# ProPrj_STM32__2025-03-02.net
KiCad netlist of a schematic drawn in EasyEDA Pro
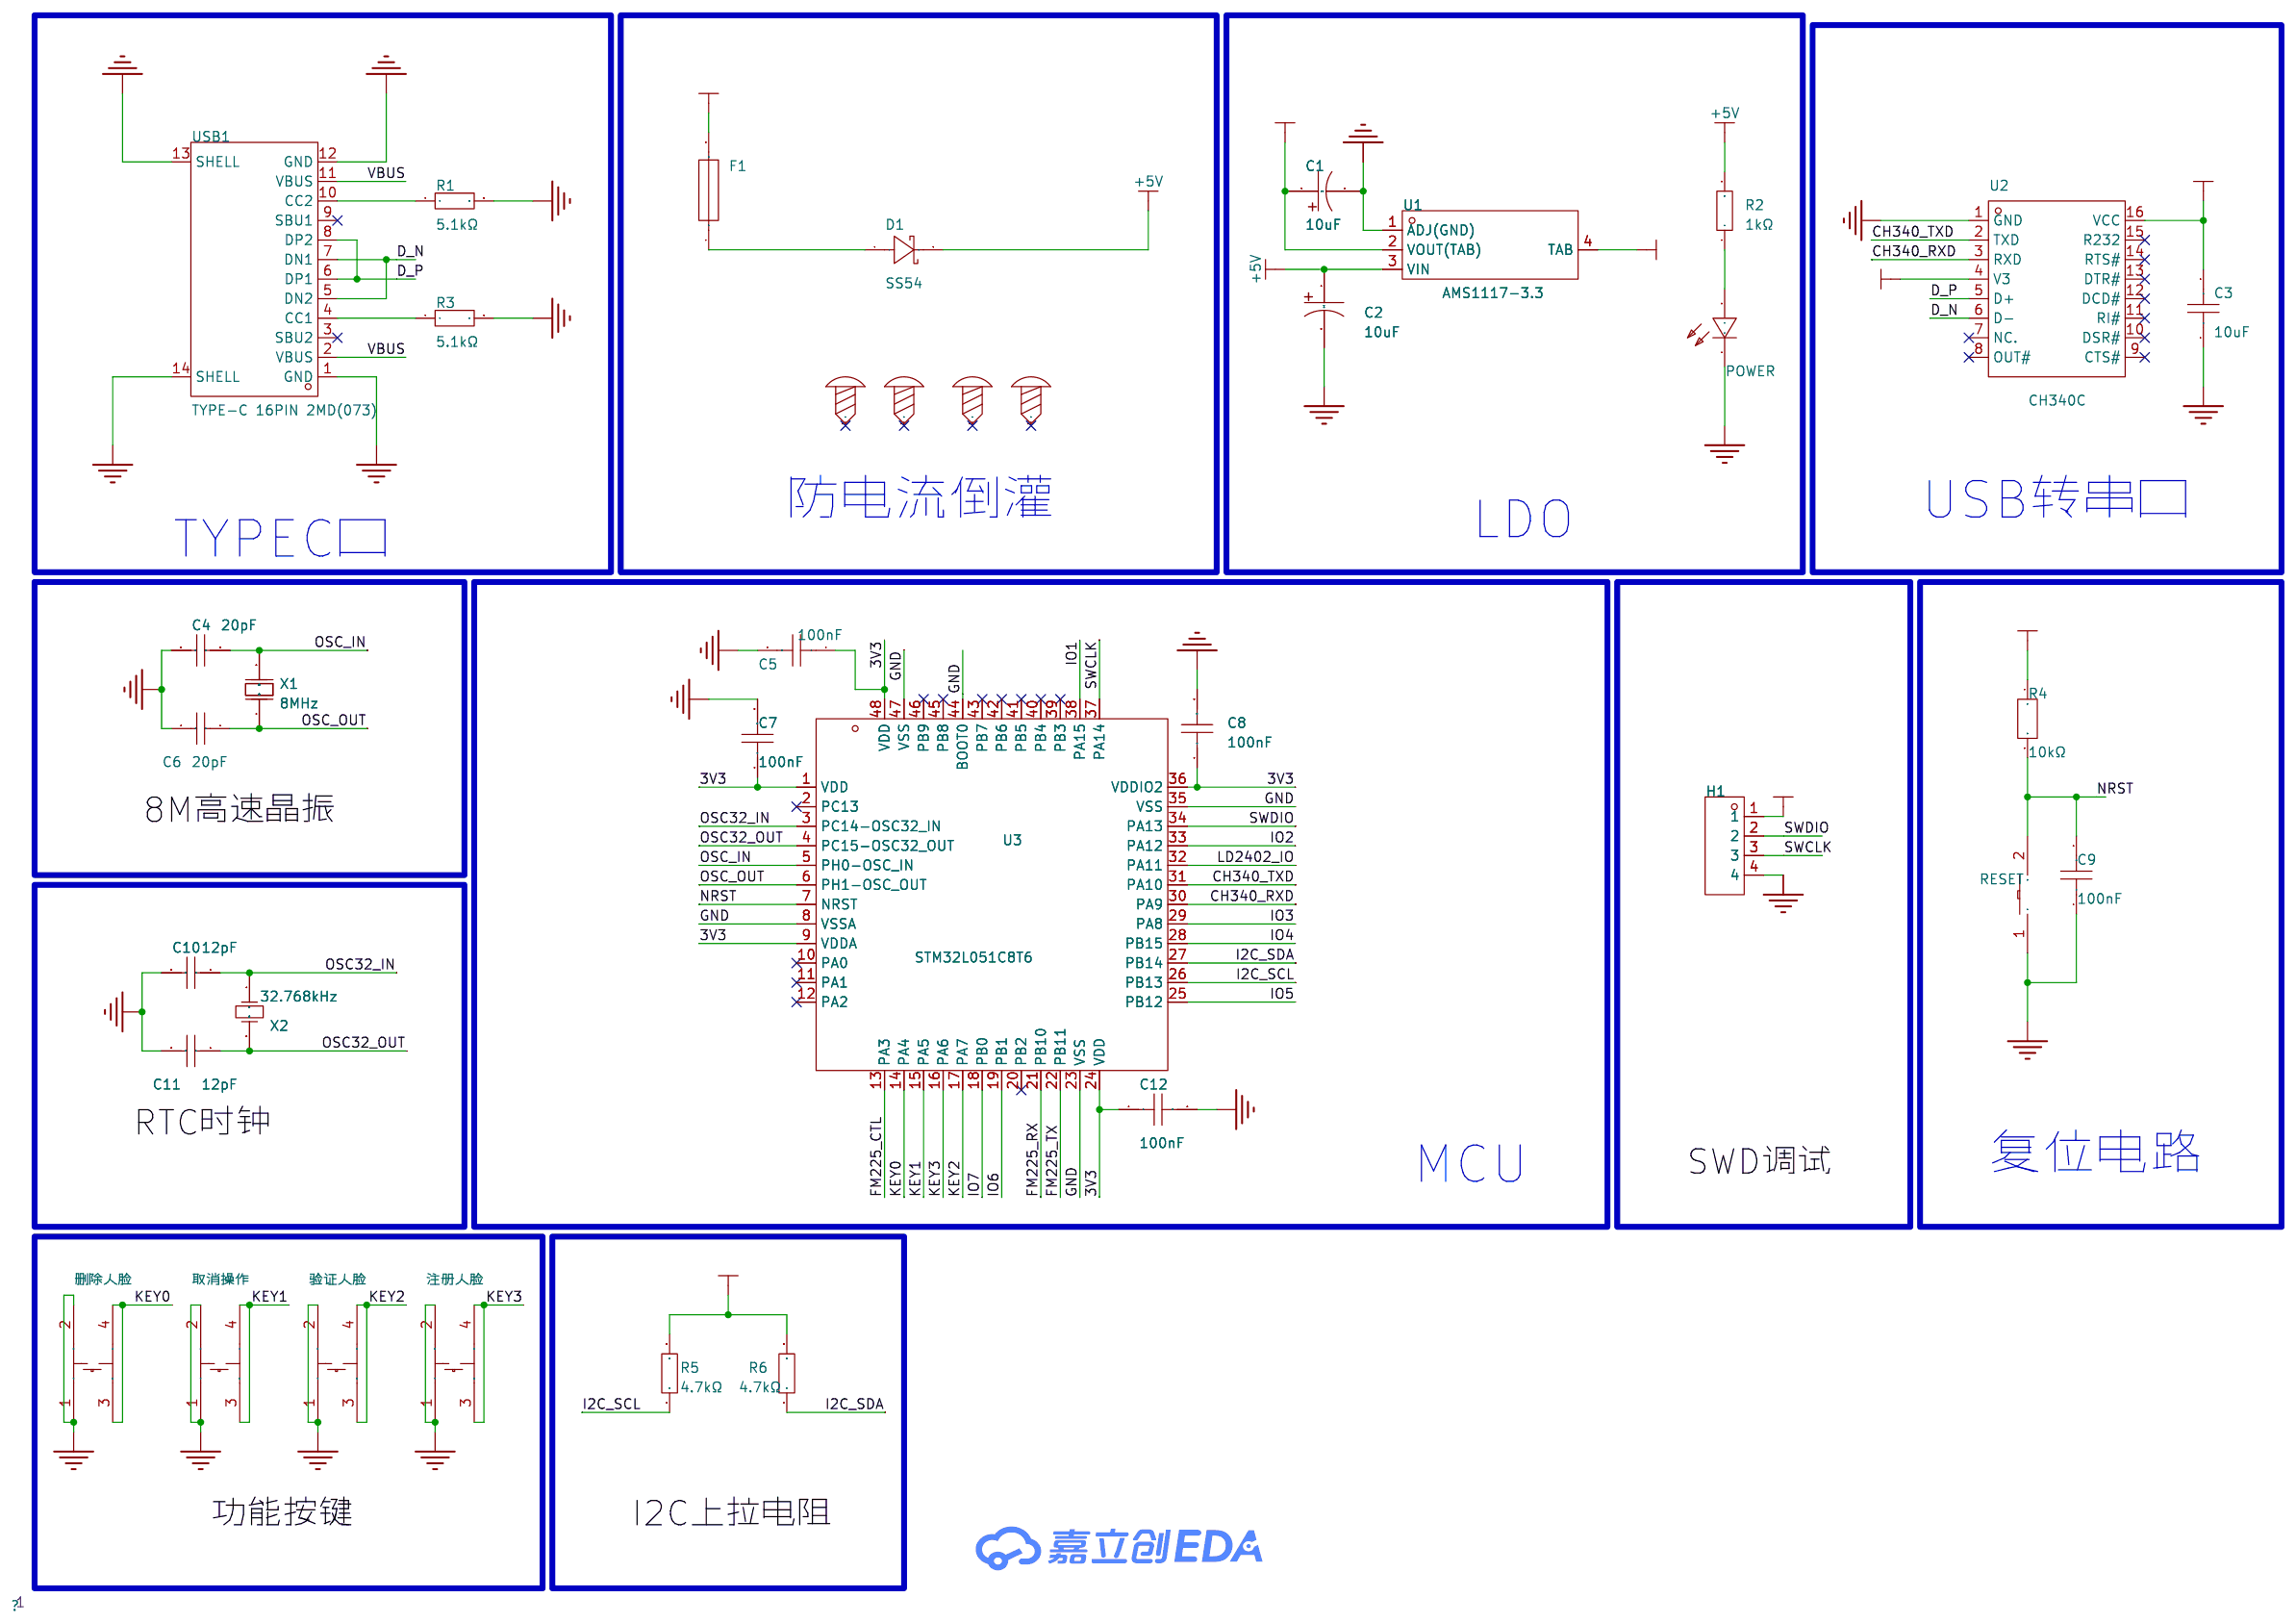
[diagram p0: STM32主控]
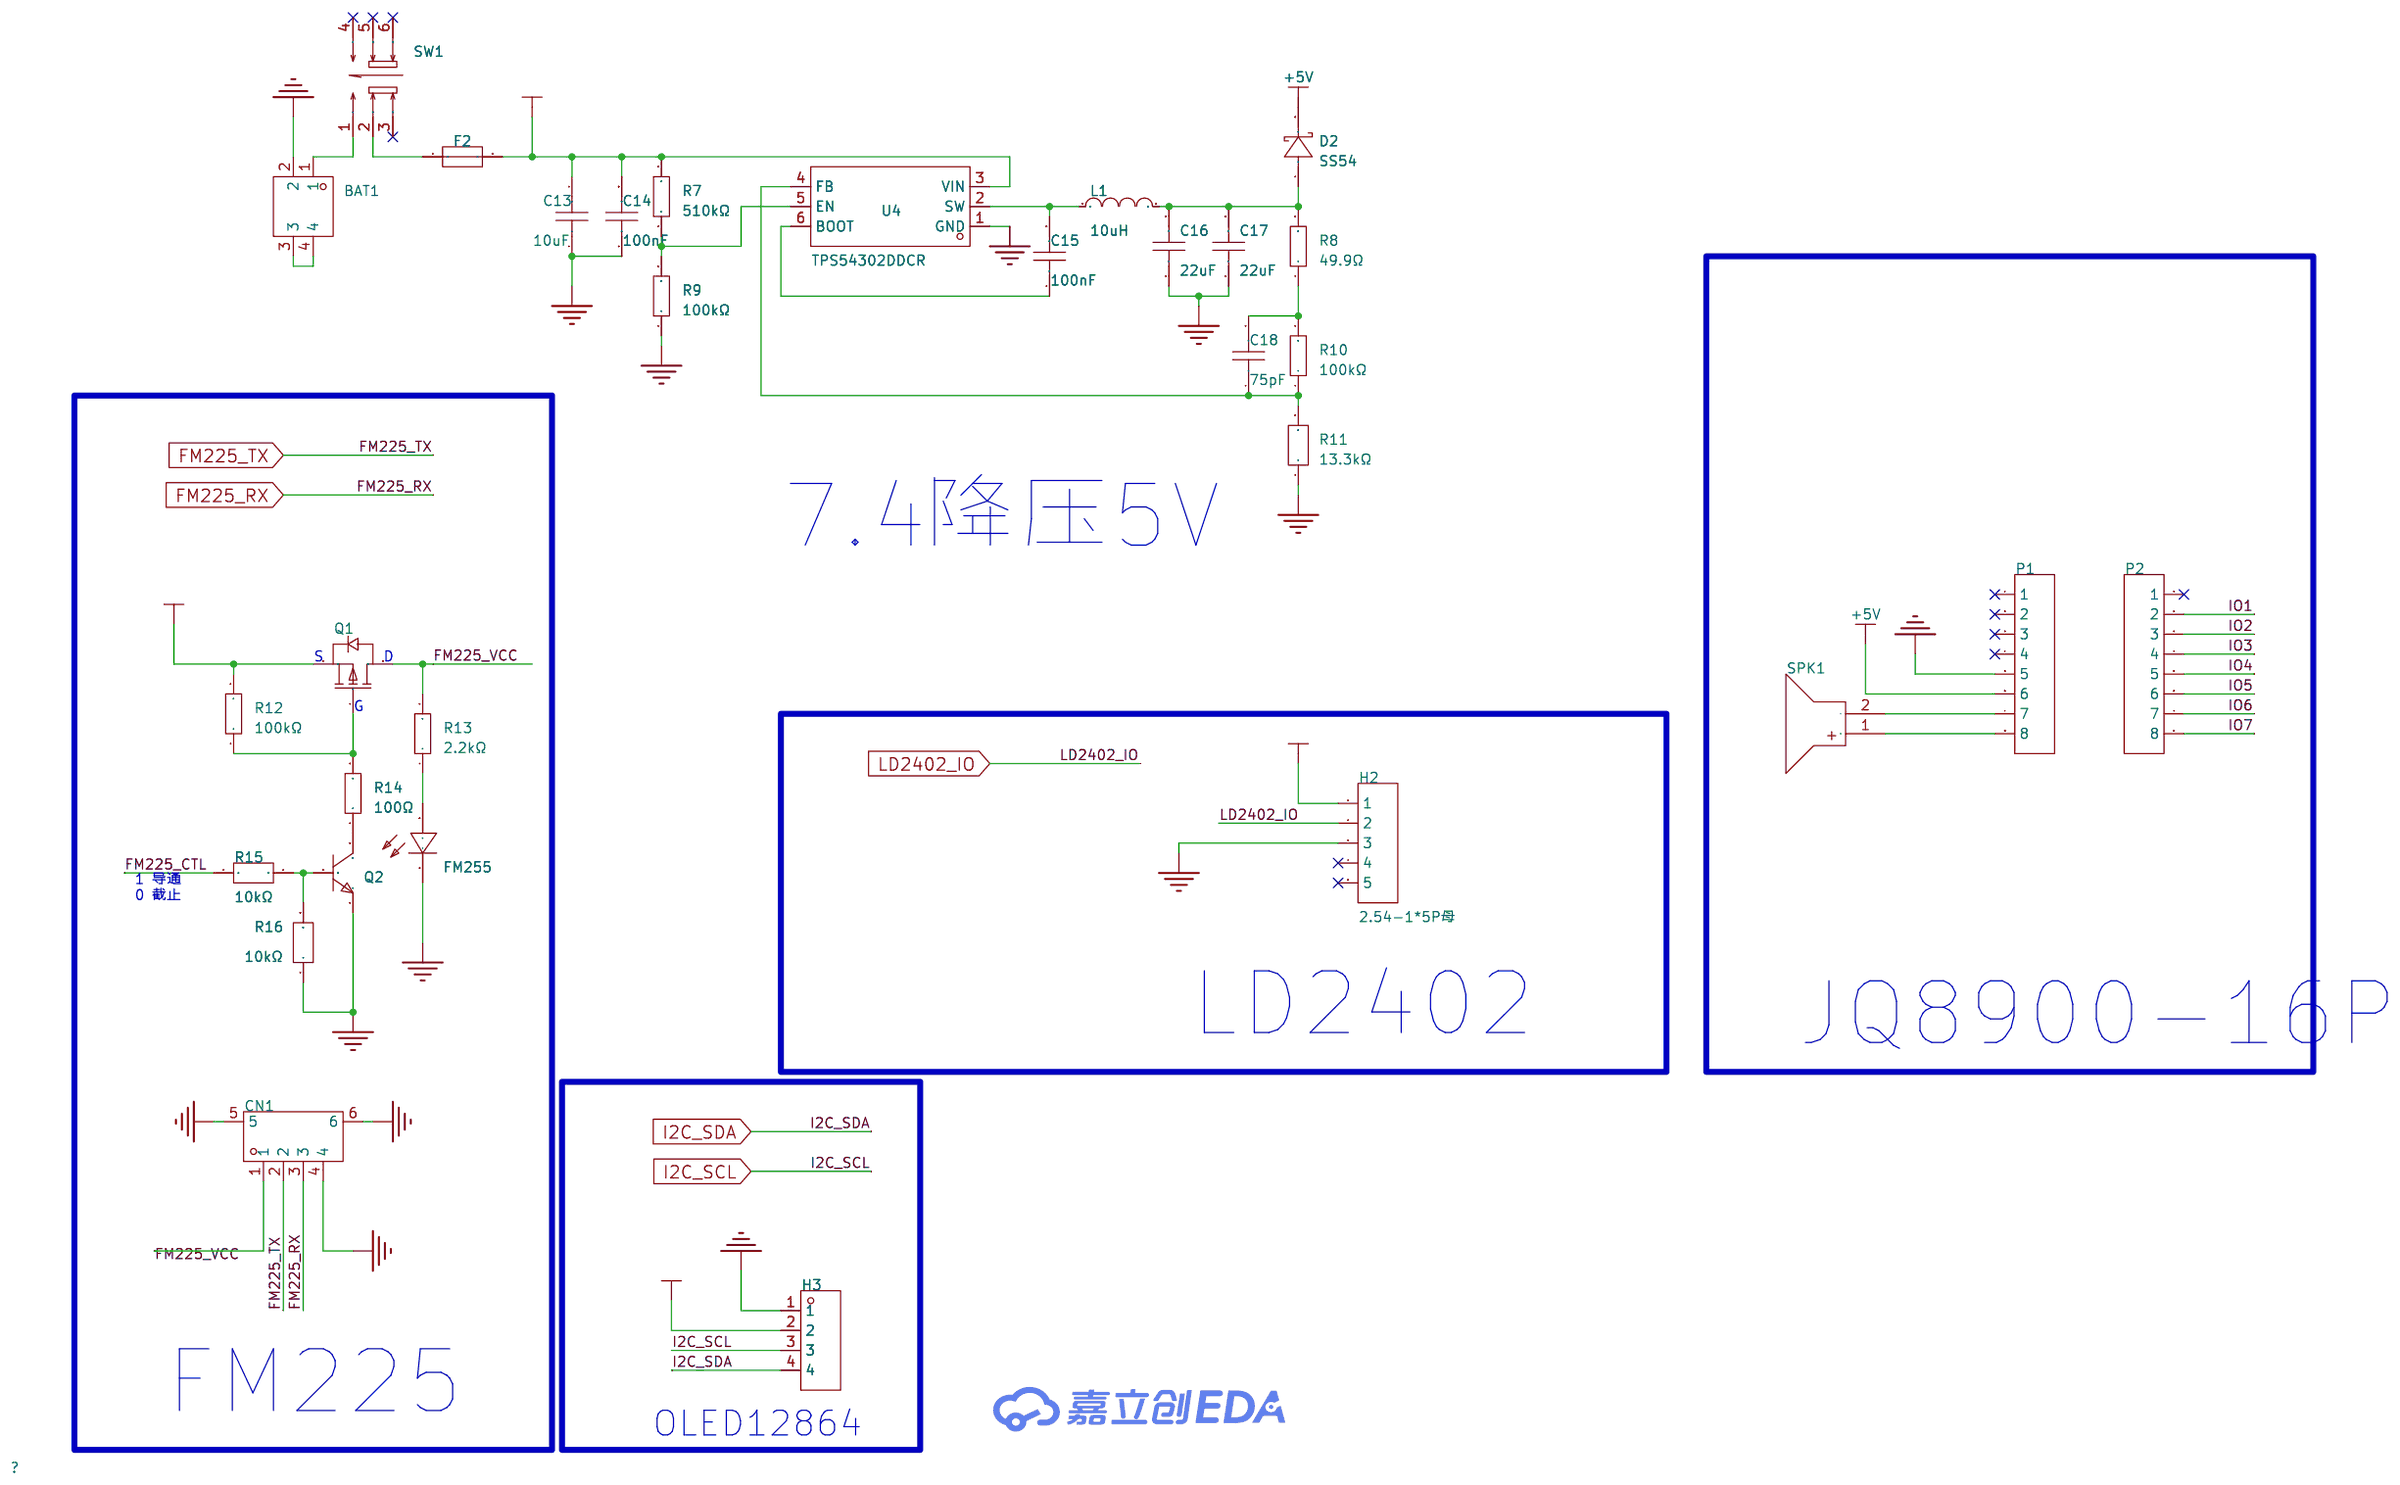
[diagram p1: other]

(export (version "E")
  (design (tool "Eeschema 10.0.6"))
  (components
    (comp (ref "C1")
      (value "10uF")
      (footprint "easyedapro:CAP-SMD_L3.2-W1.6")
      (description "容值:10uF;精度:±10%;额定电压:16V;等效串联电阻:2Ω@100kHz;")
      (fields
        (field (name "Manufacturer Part") "CA45-A-16V-10μF-K")
        (field (name "Manufacturer") "TORCH(火炬)")
      )
      (libsource (lib "easyedapro") (part "CA45-A-16V-10μF-K"))
    )
    (comp (ref "C2")
      (value "10uF")
      (footprint "easyedapro:CAP-SMD_L3.2-W1.6")
      (description "容值:10uF;精度:±10%;额定电压:16V;等效串联电阻:2Ω@100kHz;")
      (fields
        (field (name "Manufacturer Part") "CA45-A-16V-10μF-K")
        (field (name "Manufacturer") "TORCH(火炬)")
      )
      (libsource (lib "easyedapro") (part "CA45-A-16V-10μF-K"))
    )
    (comp (ref "C3")
      (value "10uF")
      (footprint "easyedapro:C0603")
      (description "容值:10uF;精度:±10%;额定电压:10V;材质(温度系数):X5R;")
      (fields
        (field (name "Manufacturer Part") "CL10A106KP8NNNC")
        (field (name "Manufacturer") "SAMSUNG(三星)")
      )
      (libsource (lib "easyedapro") (part "CL10A106KP8NNNC"))
    )
    (comp (ref "C4")
      (value "20pF")
      (footprint "easyedapro:C0603")
      (description "容值:20pF;精度:±5%;额定电压:50V;材质(温度系数):C0G;")
      (fields
        (field (name "Manufacturer Part") "CL10C200JB8NNNC")
        (field (name "Manufacturer") "SAMSUNG(三星)")
      )
      (libsource (lib "easyedapro") (part "CL10C200JB8NNNC"))
    )
    (comp (ref "C5")
      (value "100nF")
      (footprint "easyedapro:C0603")
      (description "容值:100nF;精度:±10%;额定电压:50V;材质(温度系数):X7R;")
      (fields
        (field (name "Manufacturer Part") "CGA0603X7R104K500JT")
        (field (name "Manufacturer") "HRE(芯声)")
      )
      (libsource (lib "easyedapro") (part "CGA0603X7R104K500JT"))
    )
    (comp (ref "C6")
      (value "20pF")
      (footprint "easyedapro:C0603")
      (description "容值:20pF;精度:±5%;额定电压:50V;材质(温度系数):C0G;")
      (fields
        (field (name "Manufacturer Part") "CL10C200JB8NNNC")
        (field (name "Manufacturer") "SAMSUNG(三星)")
      )
      (libsource (lib "easyedapro") (part "CL10C200JB8NNNC"))
    )
    (comp (ref "C7")
      (value "100nF")
      (footprint "easyedapro:C0603")
      (description "容值:100nF;精度:±10%;额定电压:50V;材质(温度系数):X7R;")
      (fields
        (field (name "Manufacturer Part") "CGA0603X7R104K500JT")
        (field (name "Manufacturer") "HRE(芯声)")
      )
      (libsource (lib "easyedapro") (part "CGA0603X7R104K500JT"))
    )
    (comp (ref "C8")
      (value "100nF")
      (footprint "easyedapro:C0603")
      (description "容值:100nF;精度:±10%;额定电压:50V;材质(温度系数):X7R;")
      (fields
        (field (name "Manufacturer Part") "CGA0603X7R104K500JT")
        (field (name "Manufacturer") "HRE(芯声)")
      )
      (libsource (lib "easyedapro") (part "CGA0603X7R104K500JT"))
    )
    (comp (ref "C9")
      (value "100nF")
      (footprint "easyedapro:C0603")
      (description "容值:100nF;精度:±10%;额定电压:50V;材质(温度系数):X7R;")
      (fields
        (field (name "Manufacturer Part") "CGA0603X7R104K500JT")
        (field (name "Manufacturer") "HRE(芯声)")
      )
      (libsource (lib "easyedapro") (part "CGA0603X7R104K500JT"))
    )
    (comp (ref "C10")
      (value "12pF")
      (footprint "easyedapro:C0603")
      (description "容值:12pF;精度:±5%;额定电压:50V;材质(温度系数):C0G;")
      (fields
        (field (name "Manufacturer Part") "CL10C120JB8NNNC")
        (field (name "Manufacturer") "SAMSUNG(三星)")
      )
      (libsource (lib "easyedapro") (part "CL10C120JB8NNNC"))
    )
    (comp (ref "C11")
      (value "12pF")
      (footprint "easyedapro:C0603")
      (description "容值:12pF;精度:±5%;额定电压:50V;材质(温度系数):C0G;")
      (fields
        (field (name "Manufacturer Part") "CL10C120JB8NNNC")
        (field (name "Manufacturer") "SAMSUNG(三星)")
      )
      (libsource (lib "easyedapro") (part "CL10C120JB8NNNC"))
    )
    (comp (ref "C12")
      (value "100nF")
      (footprint "easyedapro:C0603")
      (description "容值:100nF;精度:±10%;额定电压:50V;材质(温度系数):X7R;")
      (fields
        (field (name "Manufacturer Part") "CGA0603X7R104K500JT")
        (field (name "Manufacturer") "HRE(芯声)")
      )
      (libsource (lib "easyedapro") (part "CGA0603X7R104K500JT"))
    )
    (comp (ref "D1")
      (value "SS54")
      (footprint "easyedapro:SMA_L4.3-W2.6-LS5.0-FD")
      (description "二极管配置:独立式;正向压降(Vf):550mV@5.0A;直流反向耐压(Vr):40V;整流电流:5A;")
      (fields (field (name "Manufacturer") "宏迦橙"))
      (libsource (lib "easyedapro") (part "SS54_C7420369"))
    )
    (comp (ref "F1")
      (value "JK-nSMD050-30")
      (footprint "easyedapro:F1206")
      (description "最大电压:30V;最大电流:100A;保持电流:500mA;跳闸电流:1A;")
      (fields (field (name "Manufacturer") "JK(金科)"))
      (libsource (lib "easyedapro") (part "JK-NSMD050-30V"))
    )
    (comp (ref "H1")
      (value "PZ254V-11-04P")
      (footprint "easyedapro:HDR-TH_4P-P2.54-V-M")
      (fields (field (name "Manufacturer") "XFCN(兴飞)"))
      (libsource (lib "easyedapro") (part "PZ254V-11-04P_C2691448"))
    )
    (comp (ref "POWER")
      (value "NCD0603R1")
      (footprint "easyedapro:LED0603-RD_RED")
      (fields (field (name "Manufacturer") "国星光电"))
      (libsource (lib "easyedapro") (part "FC-DA1608HRK-620D"))
    )
    (comp (ref "R1")
      (value "5.1kΩ")
      (footprint "easyedapro:R0603")
      (description "电阻类型:厚膜电阻;阻值:5.1kΩ;精度:±1%;功率:100mW;最大工作电压:75V;温度系数:±100ppm/°C;")
      (fields
        (field (name "Manufacturer Part") "0603WAF5101T5E")
        (field (name "Manufacturer") "UNI-ROYAL(厚声)")
      )
      (libsource (lib "easyedapro") (part "0603WAF5101T5E"))
    )
    (comp (ref "R2")
      (value "1kΩ")
      (footprint "easyedapro:R0603")
      (description "电阻类型:厚膜电阻;阻值:1kΩ;精度:±1%;功率:100mW;最大工作电压:75V;温度系数:±100ppm/°C;")
      (fields
        (field (name "Manufacturer Part") "0603WAF1001T5E")
        (field (name "Manufacturer") "UNI-ROYAL(厚声)")
      )
      (libsource (lib "easyedapro") (part "0603WAF1001T5E"))
    )
    (comp (ref "R3")
      (value "5.1kΩ")
      (footprint "easyedapro:R0603")
      (description "电阻类型:厚膜电阻;阻值:5.1kΩ;精度:±1%;功率:100mW;最大工作电压:75V;温度系数:±100ppm/°C;")
      (fields
        (field (name "Manufacturer Part") "0603WAF5101T5E")
        (field (name "Manufacturer") "UNI-ROYAL(厚声)")
      )
      (libsource (lib "easyedapro") (part "0603WAF5101T5E"))
    )
    (comp (ref "R4")
      (value "10kΩ")
      (footprint "easyedapro:R0603")
      (description "电阻类型:厚膜电阻;阻值:10kΩ;精度:±5%;功率:100mW;最大工作电压:75V;温度系数:±100ppm/°C;")
      (fields (field (name "Manufacturer Part") "FRC0603J103TS") (field (name "Manufacturer") "FOJAN(富捷)"))
      (libsource (lib "easyedapro") (part "FRC0603J103TS"))
    )
    (comp (ref "R5")
      (value "4.7kΩ")
      (footprint "easyedapro:R0603")
      (description "电阻类型:厚膜电阻;阻值:4.7kΩ;精度:±1%;功率:100mW;最大工作电压:75V;温度系数:±100ppm/°C;")
      (fields
        (field (name "Manufacturer Part") "0603WAF4701T5E")
        (field (name "Manufacturer") "UNI-ROYAL(厚声)")
      )
      (libsource (lib "easyedapro") (part "0603WAF4701T5E"))
    )
    (comp (ref "R6")
      (value "4.7kΩ")
      (footprint "easyedapro:R0603")
      (description "电阻类型:厚膜电阻;阻值:4.7kΩ;精度:±1%;功率:100mW;最大工作电压:75V;温度系数:±100ppm/°C;")
      (fields
        (field (name "Manufacturer Part") "0603WAF4701T5E")
        (field (name "Manufacturer") "UNI-ROYAL(厚声)")
      )
      (libsource (lib "easyedapro") (part "0603WAF4701T5E"))
    )
    (comp (ref "RESET")
      (value "TS-1101-C-W")
      (footprint "easyedapro:SW-SMD_L6.0-W3.3-LS8.0")
      (fields (field (name "Manufacturer") "XKB Connectivity(中国星坤)"))
      (libsource (lib "easyedapro") (part "TS-1101-C-W"))
    )
    (comp (ref "SCREW1")
      (value "~")
      (footprint "easyedapro:M2螺丝")
      (libsource (lib "easyedapro") (part "螺丝孔"))
    )
    (comp (ref "SCREW2")
      (value "~")
      (footprint "easyedapro:M2螺丝")
      (libsource (lib "easyedapro") (part "螺丝孔"))
    )
    (comp (ref "SCREW3")
      (value "~")
      (footprint "easyedapro:M2螺丝")
      (libsource (lib "easyedapro") (part "螺丝孔"))
    )
    (comp (ref "SCREW4")
      (value "~")
      (footprint "easyedapro:M2螺丝")
      (libsource (lib "easyedapro") (part "螺丝孔"))
    )
    (comp (ref "U1")
      (value "AMS1117-3.3")
      (footprint "easyedapro:SOT-223-4_L6.5-W3.5-P2.30-LS7.0-BR")
      (description "输出类型:固定;工作电压:12V;输出电压:3.3V;输出电流:1A;电源纹波抑制比(PSRR):60dB@(120Hz);输出极性:正极;")
      (fields (field (name "Manufacturer") "UMW(友台半导体)"))
      (libsource (lib "easyedapro") (part "AMS1117-3.3_C347222"))
    )
    (comp (ref "U2")
      (value "CH340C")
      (footprint "easyedapro:SOP-16_L10.0-W3.9-P1.27-LS6.0-BL")
      (description "应用功能:收发器;接口协议:USB 2.0;数据速率:2Mbps;")
      (fields (field (name "Manufacturer") "WCH(南京沁恒)"))
      (libsource (lib "easyedapro") (part "CH340C"))
    )
    (comp (ref "U3")
      (value "STM32L051C8T6")
      (footprint "easyedapro:LQFP-48_L7.0-W7.0-P0.50-LS9.0-BL")
      (description "CPU内核:ARM-M系列;CPU最大主频:32MHz;应用领域:-;")
      (fields (field (name "Manufacturer") "ST(意法半导体)"))
      (libsource (lib "easyedapro") (part "STM32L051C8T6"))
    )
    (comp (ref "USB1")
      (value "TYPE-C 16PIN 2MD(073)")
      (footprint "easyedapro:USB-C-SMD_TYPE-C-6PIN-2MD-073")
      (description "连接器类型:Type-C;标准:USB 3.1;公母:母;安装方式:卧贴;触点数量:16P;端口数量:1;额定电流 - 电源:5A;工作温度范围:-25°C~+85°C;")
      (fields (field (name "Manufacturer") "SHOU HAN(首韩)"))
      (libsource (lib "easyedapro") (part "TYPE-C 16PIN 2MD(073)"))
    )
    (comp (ref "X1")
      (value "8MHz")
      (footprint "easyedapro:HC-49US_L11.5-W4.5-P4.88")
      (description "晶振类型:直插晶振;频率:8MHz;常温频差:±10ppm;外接负载电容:20pF;频率稳定度(全温):±30ppm;")
      (fields (field (name "Manufacturer Part") "X49SD8MSB2SI") (field (name "Manufacturer") "YXC(扬兴晶振)"))
      (libsource (lib "easyedapro") (part "X49SD8MSB2SI"))
    )
    (comp (ref "X2")
      (value "32.768kHz")
      (footprint "easyedapro:OSC-TH_BD3.1-P0.8-D0.3")
      (description "晶振类型:直插晶振;频率:32.768kHz;常温频差:±10ppm;外接负载电容:12.5pF;频率稳定度(全温):-;")
      (fields (field (name "Manufacturer Part") "X308032768KGB2SC") (field (name "Manufacturer") "YXC(扬兴晶振)"))
      (libsource (lib "easyedapro") (part "X308032768KGB2SC"))
    )
    (comp (ref "删除人脸")
      (value "TS-1002S-06026C")
      (footprint "easyedapro:KEY-SMD_4P-L6.0-W6.0-P4.50-LS9.5-BR")
      (description "电路结构:单刀单掷;按钮形状:圆形按钮;安装方式:立贴;开关长度:6mm;开关宽度:6mm;开关高度:6mm;触点电流:50mA;额定电压(DC):12V;带灯:-;机械寿命:-;")
      (fields (field (name "Manufacturer") "XUNPU(讯普)"))
      (libsource (lib "easyedapro") (part "TS-1002S-06026C"))
    )
    (comp (ref "取消操作")
      (value "TS-1002S-06026C")
      (footprint "easyedapro:KEY-SMD_4P-L6.0-W6.0-P4.50-LS9.5-BR")
      (description "电路结构:单刀单掷;按钮形状:圆形按钮;安装方式:立贴;开关长度:6mm;开关宽度:6mm;开关高度:6mm;触点电流:50mA;额定电压(DC):12V;带灯:-;机械寿命:-;")
      (fields (field (name "Manufacturer") "XUNPU(讯普)"))
      (libsource (lib "easyedapro") (part "TS-1002S-06026C"))
    )
    (comp (ref "注册人脸")
      (value "TS-1002S-06026C")
      (footprint "easyedapro:KEY-SMD_4P-L6.0-W6.0-P4.50-LS9.5-BR")
      (description "电路结构:单刀单掷;按钮形状:圆形按钮;安装方式:立贴;开关长度:6mm;开关宽度:6mm;开关高度:6mm;触点电流:50mA;额定电压(DC):12V;带灯:-;机械寿命:-;")
      (fields (field (name "Manufacturer") "XUNPU(讯普)"))
      (libsource (lib "easyedapro") (part "TS-1002S-06026C"))
    )
    (comp (ref "验证人脸")
      (value "TS-1002S-06026C")
      (footprint "easyedapro:KEY-SMD_4P-L6.0-W6.0-P4.50-LS9.5-BR")
      (description "电路结构:单刀单掷;按钮形状:圆形按钮;安装方式:立贴;开关长度:6mm;开关宽度:6mm;开关高度:6mm;触点电流:50mA;额定电压(DC):12V;带灯:-;机械寿命:-;")
      (fields (field (name "Manufacturer") "XUNPU(讯普)"))
      (libsource (lib "easyedapro") (part "TS-1002S-06026C"))
    )
    (comp (ref "BAT1")
      (value "BH-18650-A1BJ021")
      (footprint "easyedapro:BAT-TH_L77.0-W39.9_BH-18650-A1BJ021")
      (description "连接器类型:电池盒;适用电池规格:-;触点电镀:镍;工作温度范围:-25°C~+85°C;")
      (fields (field (name "Manufacturer") "MYOUNG(美阳)"))
      (libsource (lib "easyedapro") (part "BH-18650-A1BJ021"))
    )
    (comp (ref "C13")
      (value "10uF")
      (footprint "easyedapro:C0603")
      (description "容值:10uF;精度:±10%;额定电压:10V;材质(温度系数):X5R;")
      (fields
        (field (name "Manufacturer Part") "CL10A106KP8NNNC")
        (field (name "Manufacturer") "SAMSUNG(三星)")
      )
      (libsource (lib "easyedapro") (part "CL10A106KP8NNNC"))
    )
    (comp (ref "C14")
      (value "100nF")
      (footprint "easyedapro:C0603")
      (description "容值:100nF;精度:±10%;额定电压:50V;材质(温度系数):X7R;")
      (fields
        (field (name "Manufacturer Part") "CGA0603X7R104K500JT")
        (field (name "Manufacturer") "HRE(芯声)")
      )
      (libsource (lib "easyedapro") (part "CGA0603X7R104K500JT"))
    )
    (comp (ref "C15")
      (value "100nF")
      (footprint "easyedapro:C0603")
      (description "容值:100nF;精度:±10%;额定电压:50V;材质(温度系数):X7R;")
      (fields
        (field (name "Manufacturer Part") "CGA0603X7R104K500JT")
        (field (name "Manufacturer") "HRE(芯声)")
      )
      (libsource (lib "easyedapro") (part "CGA0603X7R104K500JT"))
    )
    (comp (ref "C16")
      (value "22uF")
      (footprint "easyedapro:C0603")
      (description "容值:22uF;精度:±20%;额定电压:6.3V;材质(温度系数):X5R;")
      (fields
        (field (name "Manufacturer Part") "CL10A226MQ8NRNC")
        (field (name "Manufacturer") "SAMSUNG(三星)")
      )
      (libsource (lib "easyedapro") (part "CL10A226MQ8NRNC"))
    )
    (comp (ref "C17")
      (value "22uF")
      (footprint "easyedapro:C0603")
      (description "容值:22uF;精度:±20%;额定电压:6.3V;材质(温度系数):X5R;")
      (fields
        (field (name "Manufacturer Part") "CL10A226MQ8NRNC")
        (field (name "Manufacturer") "SAMSUNG(三星)")
      )
      (libsource (lib "easyedapro") (part "CL10A226MQ8NRNC"))
    )
    (comp (ref "C18")
      (value "75pF")
      (footprint "easyedapro:C0603")
      (description "容值:75pF;精度:±5%;额定电压:50V;材质(温度系数):NP0;")
      (fields
        (field (name "Manufacturer Part") "CC0603JRNPO9BN750")
        (field (name "Manufacturer") "YAGEO(国巨)")
      )
      (libsource (lib "easyedapro") (part "CC0603JRNPO9BN750"))
    )
    (comp (ref "CN1")
      (value "HC-1.25-4PLT")
      (footprint "easyedapro:CONN-SMD_4P-P1.25_HCTL_HC-1.25-4PLT")
      (fields (field (name "Manufacturer") "HCTL(华灿天禄)"))
      (libsource (lib "easyedapro") (part "HC-1.25-4PLT"))
    )
    (comp (ref "D2")
      (value "SS54")
      (footprint "easyedapro:SMA_L4.3-W2.6-LS5.0-FD")
      (description "二极管配置:独立式;正向压降(Vf):550mV@5.0A;直流反向耐压(Vr):40V;整流电流:5A;")
      (fields (field (name "Manufacturer") "宏迦橙"))
      (libsource (lib "easyedapro") (part "SS54_C7420369"))
    )
    (comp (ref "F2")
      (value "BSMD1210-150-16V")
      (footprint "easyedapro:F1210")
      (description "最大电压:16V;最大电流:100A;保持电流:1.5A;跳闸电流:3A;")
      (fields (field (name "Manufacturer") "BHFUSE(佰宏)"))
      (libsource (lib "easyedapro") (part "BSMD1210-150-16V"))
    )
    (comp (ref "FM255")
      (value "NCD0603W3")
      (footprint "easyedapro:LED0603-RD")
      (fields (field (name "Manufacturer") "国星光电"))
      (libsource (lib "easyedapro") (part "FC-TA1608WD3-455Q"))
    )
    (comp (ref "H2")
      (value "2.54-1*5P母")
      (footprint "easyedapro:HDR-TH_5P-P2.54-V-F")
      (description "插孔结构:1x5P;间距:2.54mm;行距:-;安装类型:直插;排数:单排;总孔位数:5P;塑高:-;触头材质:-;触头镀层:-;")
      (fields (field (name "Manufacturer") "BOOMELE(博穆精密)"))
      (libsource (lib "easyedapro") (part "Header-Female-2.54_1x5"))
    )
    (comp (ref "H3")
      (value "2.54-1*4P母")
      (footprint "easyedapro:HDR-TH_4P-P2.54-V-F")
      (fields (field (name "Manufacturer") "BOOMELE(博穆精密)"))
      (libsource (lib "easyedapro") (part "2.54-1*4P母"))
    )
    (comp (ref "L1")
      (value "10uH")
      (footprint "easyedapro:IND-SMD_L7.3-W6.8")
      (description "电感值:10uH;精度:±20%;额定电流:4.5A;饱和电流(Isat):5.5A;类型:一体成型电感;")
      (fields (field (name "Manufacturer Part") "FXL0630-100-M") (field (name "Manufacturer") "cjiang(长江微电)"))
      (libsource (lib "easyedapro") (part "FXL0630-100-M"))
    )
    (comp (ref "P1")
      (value "2.54-1*8P母环保")
      (footprint "easyedapro:HDR-TH_8P-P2.54-V-F-1")
      (description "插孔结构:1x8P;间距:2.54mm;行距:-;安装类型:直插;排数:单排;总孔位数:8P;塑高:-;触头材质:-;触头镀层:-;")
      (fields (field (name "Manufacturer") "BOOMELE(博穆精密)"))
      (libsource (lib "easyedapro") (part "Header-Female-2.54_1x8"))
    )
    (comp (ref "P2")
      (value "2.54-1*8P母环保")
      (footprint "easyedapro:HDR-TH_8P-P2.54-V-F-1")
      (description "插孔结构:1x8P;间距:2.54mm;行距:-;安装类型:直插;排数:单排;总孔位数:8P;塑高:-;触头材质:-;触头镀层:-;")
      (fields (field (name "Manufacturer") "BOOMELE(博穆精密)"))
      (libsource (lib "easyedapro") (part "Header-Female-2.54_1x8"))
    )
    (comp (ref "Q1")
      (value "SI2301")
      (footprint "easyedapro:SOT-23-3_L2.9-W1.3-P1.90-LS2.4-BR")
      (fields (field (name "Manufacturer") "YONGYUTAI(永裕泰)"))
      (libsource (lib "easyedapro") (part "SI2301_C2891731"))
    )
    (comp (ref "Q2")
      (value "S8050")
      (footprint "easyedapro:SOT-23-3_L2.9-W1.3-P1.90-LS2.4-BR")
      (description "晶体管类型:NPN;集电极电流(Ic):500mA;集射极击穿电压(Vceo):25V;功率(Pd):300mW;直流电流增益(hFE@Ic,Vce):400@50mA,1V;")
      (fields (field (name "Manufacturer") "YONGYUTAI(永裕泰)"))
      (libsource (lib "easyedapro") (part "S8050_C2891804"))
    )
    (comp (ref "R7")
      (value "510kΩ")
      (footprint "easyedapro:R0603")
      (description "电阻类型:厚膜电阻;阻值:510kΩ;精度:±1%;功率:100mW;最大工作电压:75V;温度系数:±100ppm/°C;")
      (fields
        (field (name "Manufacturer Part") "0603WAF5103T5E")
        (field (name "Manufacturer") "UNI-ROYAL(厚声)")
      )
      (libsource (lib "easyedapro") (part "0603WAF5103T5E"))
    )
    (comp (ref "R8")
      (value "49.9Ω")
      (footprint "easyedapro:R0603")
      (description "电阻类型:厚膜电阻;阻值:49.9Ω;精度:±1%;功率:100mW;最大工作电压:75V;温度系数:±100ppm/°C;")
      (fields
        (field (name "Manufacturer Part") "0603WAF499JT5E")
        (field (name "Manufacturer") "UNI-ROYAL(厚声)")
      )
      (libsource (lib "easyedapro") (part "0603WAF499JT5E"))
    )
    (comp (ref "R9")
      (value "100kΩ")
      (footprint "easyedapro:R0603")
      (description "电阻类型:厚膜电阻;阻值:100kΩ;精度:±5%;功率:100mW;最大工作电压:75V;温度系数:±100ppm/°C;")
      (fields
        (field (name "Manufacturer Part") "0603WAJ0104T5E")
        (field (name "Manufacturer") "UNI-ROYAL(厚声)")
      )
      (libsource (lib "easyedapro") (part "0603WAJ0104T5E"))
    )
    (comp (ref "R10")
      (value "100kΩ")
      (footprint "easyedapro:R0603")
      (description "电阻类型:厚膜电阻;阻值:100kΩ;精度:±5%;功率:100mW;最大工作电压:75V;温度系数:±100ppm/°C;")
      (fields
        (field (name "Manufacturer Part") "0603WAJ0104T5E")
        (field (name "Manufacturer") "UNI-ROYAL(厚声)")
      )
      (libsource (lib "easyedapro") (part "0603WAJ0104T5E"))
    )
    (comp (ref "R11")
      (value "13.3kΩ")
      (footprint "easyedapro:R0603")
      (description "电阻类型:厚膜电阻;阻值:13.3kΩ;精度:±1%;功率:100mW;最大工作电压:75V;温度系数:±100ppm/°C;")
      (fields (field (name "Manufacturer Part") "FRC0603F1332TS") (field (name "Manufacturer") "FOJAN(富捷)"))
      (libsource (lib "easyedapro") (part "FRC0603F1332TS"))
    )
    (comp (ref "R12")
      (value "100kΩ")
      (footprint "easyedapro:R0603")
      (description "电阻类型:厚膜电阻;阻值:100kΩ;精度:±5%;功率:100mW;最大工作电压:75V;温度系数:±100ppm/°C;")
      (fields
        (field (name "Manufacturer Part") "0603WAJ0104T5E")
        (field (name "Manufacturer") "UNI-ROYAL(厚声)")
      )
      (libsource (lib "easyedapro") (part "0603WAJ0104T5E"))
    )
    (comp (ref "R13")
      (value "2.2kΩ")
      (footprint "easyedapro:R0603")
      (description "电阻类型:厚膜电阻;阻值:2.2kΩ;精度:±1%;功率:100mW;最大工作电压:75V;温度系数:±100ppm/°C;")
      (fields
        (field (name "Manufacturer Part") "0603WAF2201T5E")
        (field (name "Manufacturer") "UNI-ROYAL(厚声)")
      )
      (libsource (lib "easyedapro") (part "0603WAF2201T5E"))
    )
    (comp (ref "R14")
      (value "100Ω")
      (footprint "easyedapro:R0603")
      (description "电阻类型:厚膜电阻;阻值:100Ω;精度:±1%;功率:100mW;最大工作电压:75V;温度系数:±200ppm/°C;")
      (fields
        (field (name "Manufacturer Part") "0603WAF1000T5E")
        (field (name "Manufacturer") "UNI-ROYAL(厚声)")
      )
      (libsource (lib "easyedapro") (part "0603WAF1000T5E"))
    )
    (comp (ref "R15")
      (value "10kΩ")
      (footprint "easyedapro:R0603")
      (description "电阻类型:厚膜电阻;阻值:10kΩ;精度:±5%;功率:100mW;最大工作电压:75V;温度系数:±100ppm/°C;")
      (fields (field (name "Manufacturer Part") "FRC0603J103TS") (field (name "Manufacturer") "FOJAN(富捷)"))
      (libsource (lib "easyedapro") (part "FRC0603J103TS"))
    )
    (comp (ref "R16")
      (value "10kΩ")
      (footprint "easyedapro:R0603")
      (description "电阻类型:厚膜电阻;阻值:10kΩ;精度:±5%;功率:100mW;最大工作电压:75V;温度系数:±100ppm/°C;")
      (fields (field (name "Manufacturer Part") "FRC0603J103TS") (field (name "Manufacturer") "FOJAN(富捷)"))
      (libsource (lib "easyedapro") (part "FRC0603J103TS"))
    )
    (comp (ref "SPK1")
      (value "GSPK2307P-8R1W")
      (footprint "easyedapro:SPK-TH_BD23.0-P10.00-D0.8-L-RD")
      (fields (field (name "Manufacturer") "INGHAi(赢海)"))
      (libsource (lib "easyedapro") (part "GSPK2307P-8R1W"))
    )
    (comp (ref "SW1")
      (value "XKB7070-Z")
      (footprint "easyedapro:SW-TH_6P-L7.0-W7.0-P2.00")
      (description "自锁/无锁:自锁;安装方式:直插;触点电流:100mA;额定电压 (AC):250V;额定电压 (DC):30V;带灯:不带;作用力:160gf;机械寿命:10万次;")
      (fields (field (name "Manufacturer") "XKB Connectivity(中国星坤)"))
      (libsource (lib "easyedapro") (part "XKB7070-Z"))
    )
    (comp (ref "U4")
      (value "TPS54302DDCR")
      (footprint "easyedapro:SOT-23-6_L2.9-W1.6-P0.95-LS2.8-BL")
      (description "功能类型:降压型;输出类型:固定;工作电压:4.5V~28V;输出电压:5V;输出电流:3A;")
      (fields (field (name "Manufacturer") "TI(德州仪器)"))
      (libsource (lib "easyedapro") (part "TPS54302DDCR_C311983"))
    )
  )
  (nets
    (net (code "1") (name "+5V") (class "Default")
      (node (ref "C2") (pin "1") (pinfunction "1_1") (pintype "unspecified"))
      (node (ref "D1") (pin "2") (pinfunction "K_2") (pintype "unspecified"))
      (node (ref "D2") (pin "2") (pinfunction "K_2") (pintype "unspecified"))
      (node (ref "P1") (pin "6") (pinfunction "6_6") (pintype "input"))
      (node (ref "R2") (pin "2") (pinfunction "2_2") (pintype "input"))
      (node (ref "U1") (pin "3") (pinfunction "VIN_3") (pintype "unspecified"))
    )
    (net (code "2") (name "3V3") (class "Default")
      (node (ref "C1") (pin "1") (pinfunction "1_1") (pintype "unspecified"))
      (node (ref "C12") (pin "1") (pinfunction "1_1") (pintype "unspecified"))
      (node (ref "C3") (pin "2") (pinfunction "2_2") (pintype "unspecified"))
      (node (ref "C5") (pin "1") (pinfunction "1_1") (pintype "unspecified"))
      (node (ref "C7") (pin "1") (pinfunction "1_1") (pintype "unspecified"))
      (node (ref "C8") (pin "1") (pinfunction "1_1") (pintype "unspecified"))
      (node (ref "H1") (pin "1") (pinfunction "1_1") (pintype "unspecified"))
      (node (ref "H2") (pin "1") (pinfunction "1_1") (pintype "input"))
      (node (ref "H3") (pin "2") (pinfunction "2_2") (pintype "unspecified"))
      (node (ref "R4") (pin "1") (pinfunction "1_1") (pintype "unspecified"))
      (node (ref "R5") (pin "2") (pinfunction "2_2") (pintype "input"))
      (node (ref "R6") (pin "2") (pinfunction "2_2") (pintype "input"))
      (node (ref "U1") (pin "2") (pinfunction "VOUT(TAB)_2") (pintype "unspecified"))
      (node (ref "U1") (pin "4") (pinfunction "TAB_4") (pintype "unspecified"))
      (node (ref "U2") (pin "16") (pinfunction "VCC_16") (pintype "unspecified"))
      (node (ref "U2") (pin "4") (pinfunction "V3_4") (pintype "unspecified"))
      (node (ref "U3") (pin "1") (pinfunction "VDD_1") (pintype "unspecified"))
      (node (ref "U3") (pin "24") (pinfunction "VDD_24") (pintype "unspecified"))
      (node (ref "U3") (pin "36") (pinfunction "VDDIO2_36") (pintype "unspecified"))
      (node (ref "U3") (pin "48") (pinfunction "VDD_48") (pintype "unspecified"))
      (node (ref "U3") (pin "9") (pinfunction "VDDA_9") (pintype "unspecified"))
    )
    (net (code "3") (name "7V4") (class "Default")
      (node (ref "C13") (pin "2") (pinfunction "2_2") (pintype "unspecified"))
      (node (ref "C14") (pin "2") (pinfunction "2_2") (pintype "unspecified"))
      (node (ref "F2") (pin "2") (pinfunction "2_2") (pintype "unspecified"))
      (node (ref "Q1") (pin "2") (pinfunction "S_2") (pintype "unspecified"))
      (node (ref "R12") (pin "2") (pinfunction "2_2") (pintype "input"))
      (node (ref "R7") (pin "2") (pinfunction "2_2") (pintype "input"))
      (node (ref "U4") (pin "3") (pinfunction "VIN_3") (pintype "unspecified"))
    )
    (net (code "4") (name "CH340_RXD") (class "Default")
      (node (ref "U2") (pin "3") (pinfunction "RXD_3") (pintype "unspecified"))
      (node (ref "U3") (pin "30") (pinfunction "PA9_30") (pintype "unspecified"))
    )
    (net (code "5") (name "CH340_TXD") (class "Default")
      (node (ref "U2") (pin "2") (pinfunction "TXD_2") (pintype "unspecified"))
      (node (ref "U3") (pin "31") (pinfunction "PA10_31") (pintype "unspecified"))
    )
    (net (code "6") (name "D_N") (class "Default")
      (node (ref "U2") (pin "6") (pinfunction "D-_6") (pintype "unspecified"))
      (node (ref "USB1") (pin "5") (pinfunction "DN2_5") (pintype "unspecified"))
      (node (ref "USB1") (pin "7") (pinfunction "DN1_7") (pintype "unspecified"))
    )
    (net (code "7") (name "D_P") (class "Default")
      (node (ref "U2") (pin "5") (pinfunction "D+_5") (pintype "unspecified"))
      (node (ref "USB1") (pin "6") (pinfunction "DP1_6") (pintype "unspecified"))
      (node (ref "USB1") (pin "8") (pinfunction "DP2_8") (pintype "unspecified"))
    )
    (net (code "8") (name "FM225_CTL") (class "Default")
      (node (ref "R15") (pin "2") (pinfunction "2_2") (pintype "unspecified"))
      (node (ref "U3") (pin "13") (pinfunction "PA3_13") (pintype "unspecified"))
    )
    (net (code "9") (name "FM225_RX") (class "Default")
      (node (ref "CN1") (pin "3") (pinfunction "3_3") (pintype "unspecified"))
      (node (ref "U3") (pin "21") (pinfunction "PB10_21") (pintype "unspecified"))
    )
    (net (code "10") (name "FM225_TX") (class "Default")
      (node (ref "CN1") (pin "2") (pinfunction "2_2") (pintype "unspecified"))
      (node (ref "U3") (pin "22") (pinfunction "PB11_22") (pintype "unspecified"))
    )
    (net (code "11") (name "FM225_VCC") (class "Default")
      (node (ref "CN1") (pin "1") (pinfunction "1_1") (pintype "unspecified"))
      (node (ref "Q1") (pin "3") (pinfunction "D_3") (pintype "unspecified"))
      (node (ref "R13") (pin "2") (pinfunction "2_2") (pintype "input"))
    )
    (net (code "12") (name "GND") (class "Default")
      (node (ref "BAT1") (pin "2") (pinfunction "2_2") (pintype "unspecified"))
      (node (ref "C1") (pin "2") (pinfunction "2_2") (pintype "unspecified"))
      (node (ref "C10") (pin "2") (pinfunction "2_2") (pintype "input"))
      (node (ref "C11") (pin "2") (pinfunction "2_2") (pintype "input"))
      (node (ref "C12") (pin "2") (pinfunction "2_2") (pintype "unspecified"))
      (node (ref "C13") (pin "1") (pinfunction "1_1") (pintype "unspecified"))
      (node (ref "C14") (pin "1") (pinfunction "1_1") (pintype "unspecified"))
      (node (ref "C16") (pin "1") (pinfunction "1_1") (pintype "unspecified"))
      (node (ref "C17") (pin "1") (pinfunction "1_1") (pintype "unspecified"))
      (node (ref "C2") (pin "2") (pinfunction "2_2") (pintype "unspecified"))
      (node (ref "C3") (pin "1") (pinfunction "1_1") (pintype "unspecified"))
      (node (ref "C4") (pin "2") (pinfunction "2_2") (pintype "input"))
      (node (ref "C5") (pin "2") (pinfunction "2_2") (pintype "unspecified"))
      (node (ref "C6") (pin "2") (pinfunction "2_2") (pintype "input"))
      (node (ref "C7") (pin "2") (pinfunction "2_2") (pintype "unspecified"))
      (node (ref "C8") (pin "2") (pinfunction "2_2") (pintype "unspecified"))
      (node (ref "C9") (pin "1") (pinfunction "1_1") (pintype "unspecified"))
      (node (ref "CN1") (pin "4") (pinfunction "4_4") (pintype "unspecified"))
      (node (ref "CN1") (pin "5") (pinfunction "5_5") (pintype "unspecified"))
      (node (ref "CN1") (pin "6") (pinfunction "6_6") (pintype "unspecified"))
      (node (ref "FM255") (pin "1") (pinfunction "-_1") (pintype "unspecified"))
      (node (ref "H1") (pin "4") (pinfunction "4_4") (pintype "unspecified"))
      (node (ref "H2") (pin "3") (pinfunction "3_3") (pintype "input"))
      (node (ref "H3") (pin "1") (pinfunction "1_1") (pintype "unspecified"))
      (node (ref "P1") (pin "5") (pinfunction "5_5") (pintype "input"))
      (node (ref "POWER") (pin "1") (pinfunction "K_1") (pintype "input"))
      (node (ref "Q2") (pin "2") (pinfunction "E_2") (pintype "unspecified"))
      (node (ref "R1") (pin "2") (pinfunction "2_2") (pintype "input"))
      (node (ref "R11") (pin "1") (pinfunction "1_1") (pintype "unspecified"))
      (node (ref "R16") (pin "1") (pinfunction "1_1") (pintype "unspecified"))
      (node (ref "R3") (pin "2") (pinfunction "2_2") (pintype "input"))
      (node (ref "R9") (pin "1") (pinfunction "1_1") (pintype "input"))
      (node (ref "RESET") (pin "1") (pinfunction "1_1") (pintype "unspecified"))
      (node (ref "U1") (pin "1") (pinfunction "ADJ(GND)_1") (pintype "unspecified"))
      (node (ref "U2") (pin "1") (pinfunction "GND_1") (pintype "unspecified"))
      (node (ref "U3") (pin "23") (pinfunction "VSS_23") (pintype "unspecified"))
      (node (ref "U3") (pin "35") (pinfunction "VSS_35") (pintype "unspecified"))
      (node (ref "U3") (pin "44") (pinfunction "BOOT0_44") (pintype "unspecified"))
      (node (ref "U3") (pin "47") (pinfunction "VSS_47") (pintype "unspecified"))
      (node (ref "U3") (pin "8") (pinfunction "VSSA_8") (pintype "unspecified"))
      (node (ref "U4") (pin "1") (pinfunction "GND_1") (pintype "unspecified"))
      (node (ref "USB1") (pin "1") (pinfunction "GND_1") (pintype "unspecified"))
      (node (ref "USB1") (pin "12") (pinfunction "GND_12") (pintype "unspecified"))
      (node (ref "USB1") (pin "13") (pinfunction "SHELL_13") (pintype "unspecified"))
      (node (ref "USB1") (pin "14") (pinfunction "SHELL_14") (pintype "unspecified"))
      (node (ref "删除人脸") (pin "1") (pinfunction "1_1") (pintype "unspecified"))
      (node (ref "删除人脸") (pin "2") (pinfunction "2_2") (pintype "unspecified"))
      (node (ref "取消操作") (pin "1") (pinfunction "1_1") (pintype "unspecified"))
      (node (ref "取消操作") (pin "2") (pinfunction "2_2") (pintype "unspecified"))
      (node (ref "注册人脸") (pin "1") (pinfunction "1_1") (pintype "unspecified"))
      (node (ref "注册人脸") (pin "2") (pinfunction "2_2") (pintype "unspecified"))
      (node (ref "验证人脸") (pin "1") (pinfunction "1_1") (pintype "unspecified"))
      (node (ref "验证人脸") (pin "2") (pinfunction "2_2") (pintype "unspecified"))
    )
    (net (code "13") (name "I2C_SCL") (class "Default")
      (node (ref "H3") (pin "3") (pinfunction "3_3") (pintype "unspecified"))
      (node (ref "R5") (pin "1") (pinfunction "1_1") (pintype "input"))
      (node (ref "U3") (pin "26") (pinfunction "PB13_26") (pintype "unspecified"))
    )
    (net (code "14") (name "I2C_SDA") (class "Default")
      (node (ref "H3") (pin "4") (pinfunction "4_4") (pintype "unspecified"))
      (node (ref "R6") (pin "1") (pinfunction "1_1") (pintype "input"))
      (node (ref "U3") (pin "27") (pinfunction "PB14_27") (pintype "unspecified"))
    )
    (net (code "15") (name "IO1") (class "Default")
      (node (ref "P2") (pin "2") (pinfunction "2_2") (pintype "input"))
      (node (ref "U3") (pin "38") (pinfunction "PA15_38") (pintype "unspecified"))
    )
    (net (code "16") (name "IO2") (class "Default")
      (node (ref "P2") (pin "3") (pinfunction "3_3") (pintype "input"))
      (node (ref "U3") (pin "33") (pinfunction "PA12_33") (pintype "unspecified"))
    )
    (net (code "17") (name "IO3") (class "Default")
      (node (ref "P2") (pin "4") (pinfunction "4_4") (pintype "input"))
      (node (ref "U3") (pin "29") (pinfunction "PA8_29") (pintype "unspecified"))
    )
    (net (code "18") (name "IO4") (class "Default")
      (node (ref "P2") (pin "5") (pinfunction "5_5") (pintype "input"))
      (node (ref "U3") (pin "28") (pinfunction "PB15_28") (pintype "unspecified"))
    )
    (net (code "19") (name "IO5") (class "Default")
      (node (ref "P2") (pin "6") (pinfunction "6_6") (pintype "input"))
      (node (ref "U3") (pin "25") (pinfunction "PB12_25") (pintype "unspecified"))
    )
    (net (code "20") (name "IO6") (class "Default")
      (node (ref "P2") (pin "7") (pinfunction "7_7") (pintype "input"))
      (node (ref "U3") (pin "19") (pinfunction "PB1_19") (pintype "unspecified"))
    )
    (net (code "21") (name "IO7") (class "Default")
      (node (ref "P2") (pin "8") (pinfunction "8_8") (pintype "input"))
      (node (ref "U3") (pin "18") (pinfunction "PB0_18") (pintype "unspecified"))
    )
    (net (code "22") (name "KEY0") (class "Default")
      (node (ref "U3") (pin "14") (pinfunction "PA4_14") (pintype "unspecified"))
      (node (ref "删除人脸") (pin "3") (pinfunction "3_3") (pintype "unspecified"))
      (node (ref "删除人脸") (pin "4") (pinfunction "4_4") (pintype "unspecified"))
    )
    (net (code "23") (name "KEY1") (class "Default")
      (node (ref "U3") (pin "15") (pinfunction "PA5_15") (pintype "unspecified"))
      (node (ref "取消操作") (pin "3") (pinfunction "3_3") (pintype "unspecified"))
      (node (ref "取消操作") (pin "4") (pinfunction "4_4") (pintype "unspecified"))
    )
    (net (code "24") (name "KEY2") (class "Default")
      (node (ref "U3") (pin "17") (pinfunction "PA7_17") (pintype "unspecified"))
      (node (ref "验证人脸") (pin "3") (pinfunction "3_3") (pintype "unspecified"))
      (node (ref "验证人脸") (pin "4") (pinfunction "4_4") (pintype "unspecified"))
    )
    (net (code "25") (name "KEY3") (class "Default")
      (node (ref "U3") (pin "16") (pinfunction "PA6_16") (pintype "unspecified"))
      (node (ref "注册人脸") (pin "3") (pinfunction "3_3") (pintype "unspecified"))
      (node (ref "注册人脸") (pin "4") (pinfunction "4_4") (pintype "unspecified"))
    )
    (net (code "26") (name "LD2402_IO") (class "Default")
      (node (ref "H2") (pin "2") (pinfunction "2_2") (pintype "input"))
      (node (ref "U3") (pin "32") (pinfunction "PA11_32") (pintype "unspecified"))
    )
    (net (code "27") (name "NRST") (class "Default")
      (node (ref "C9") (pin "2") (pinfunction "2_2") (pintype "unspecified"))
      (node (ref "R4") (pin "2") (pinfunction "2_2") (pintype "unspecified"))
      (node (ref "RESET") (pin "2") (pinfunction "2_2") (pintype "unspecified"))
      (node (ref "U3") (pin "7") (pinfunction "NRST_7") (pintype "unspecified"))
    )
    (net (code "28") (name "Net-(BAT1-Pad1)") (class "Default")
      (node (ref "BAT1") (pin "1") (pinfunction "1_1") (pintype "unspecified"))
      (node (ref "SW1") (pin "1") (pinfunction "1_1") (pintype "unspecified"))
    )
    (net (code "29") (name "Net-(BAT1-Pad3)") (class "Default")
      (node (ref "BAT1") (pin "3") (pinfunction "3_3") (pintype "unspecified"))
      (node (ref "BAT1") (pin "4") (pinfunction "4_4") (pintype "unspecified"))
    )
    (net (code "30") (name "Net-(C18-Pad2)") (class "Default")
      (node (ref "C18") (pin "2") (pinfunction "2_2") (pintype "unspecified"))
      (node (ref "R10") (pin "2") (pinfunction "2_2") (pintype "input"))
      (node (ref "R8") (pin "1") (pinfunction "1_1") (pintype "input"))
    )
    (net (code "31") (name "Net-(D1-A)") (class "Default")
      (node (ref "D1") (pin "1") (pinfunction "A_1") (pintype "unspecified"))
      (node (ref "F1") (pin "1") (pinfunction "1_1") (pintype "unspecified"))
    )
    (net (code "32") (name "Net-(D2-A)") (class "Default")
      (node (ref "C16") (pin "2") (pinfunction "2_2") (pintype "unspecified"))
      (node (ref "C17") (pin "2") (pinfunction "2_2") (pintype "unspecified"))
      (node (ref "D2") (pin "1") (pinfunction "A_1") (pintype "unspecified"))
      (node (ref "L1") (pin "2") (pinfunction "2_2") (pintype "unspecified"))
      (node (ref "R8") (pin "2") (pinfunction "2_2") (pintype "input"))
    )
    (net (code "33") (name "Net-(F2-Pad1)") (class "Default")
      (node (ref "F2") (pin "1") (pinfunction "1_1") (pintype "unspecified"))
      (node (ref "SW1") (pin "2") (pinfunction "2_2") (pintype "unspecified"))
    )
    (net (code "34") (name "Net-(FM255-+)") (class "Default")
      (node (ref "FM255") (pin "2") (pinfunction "+_2") (pintype "unspecified"))
      (node (ref "R13") (pin "1") (pinfunction "1_1") (pintype "input"))
    )
    (net (code "35") (name "Net-(POWER-A)") (class "Default")
      (node (ref "POWER") (pin "2") (pinfunction "A_2") (pintype "input"))
      (node (ref "R2") (pin "1") (pinfunction "1_1") (pintype "input"))
    )
    (net (code "36") (name "Net-(Q1-G)") (class "Default")
      (node (ref "Q1") (pin "1") (pinfunction "G_1") (pintype "unspecified"))
      (node (ref "R12") (pin "1") (pinfunction "1_1") (pintype "input"))
      (node (ref "R14") (pin "2") (pinfunction "2_2") (pintype "input"))
    )
    (net (code "37") (name "Net-(Q2-B)") (class "Default")
      (node (ref "Q2") (pin "1") (pinfunction "B_1") (pintype "unspecified"))
      (node (ref "R15") (pin "1") (pinfunction "1_1") (pintype "unspecified"))
      (node (ref "R16") (pin "2") (pinfunction "2_2") (pintype "unspecified"))
    )
    (net (code "38") (name "Net-(Q2-C)") (class "Default")
      (node (ref "Q2") (pin "3") (pinfunction "C_3") (pintype "unspecified"))
      (node (ref "R14") (pin "1") (pinfunction "1_1") (pintype "input"))
    )
    (net (code "39") (name "Net-(SPK1-+)") (class "Default")
      (node (ref "P1") (pin "8") (pinfunction "8_8") (pintype "input"))
      (node (ref "SPK1") (pin "1") (pinfunction "+_1") (pintype "unspecified"))
    )
    (net (code "40") (name "Net-(SPK1--)") (class "Default")
      (node (ref "P1") (pin "7") (pinfunction "7_7") (pintype "input"))
      (node (ref "SPK1") (pin "2") (pinfunction "-_2") (pintype "unspecified"))
    )
    (net (code "41") (name "Net-(U4-BOOT)") (class "Default")
      (node (ref "C15") (pin "1") (pinfunction "1_1") (pintype "unspecified"))
      (node (ref "U4") (pin "6") (pinfunction "BOOT_6") (pintype "unspecified"))
    )
    (net (code "42") (name "Net-(U4-EN)") (class "Default")
      (node (ref "R7") (pin "1") (pinfunction "1_1") (pintype "input"))
      (node (ref "R9") (pin "2") (pinfunction "2_2") (pintype "input"))
      (node (ref "U4") (pin "5") (pinfunction "EN_5") (pintype "unspecified"))
    )
    (net (code "43") (name "Net-(U4-FB)") (class "Default")
      (node (ref "C18") (pin "1") (pinfunction "1_1") (pintype "unspecified"))
      (node (ref "R10") (pin "1") (pinfunction "1_1") (pintype "input"))
      (node (ref "R11") (pin "2") (pinfunction "2_2") (pintype "unspecified"))
      (node (ref "U4") (pin "4") (pinfunction "FB_4") (pintype "unspecified"))
    )
    (net (code "44") (name "Net-(U4-SW)") (class "Default")
      (node (ref "C15") (pin "2") (pinfunction "2_2") (pintype "unspecified"))
      (node (ref "L1") (pin "1") (pinfunction "1_1") (pintype "unspecified"))
      (node (ref "U4") (pin "2") (pinfunction "SW_2") (pintype "unspecified"))
    )
    (net (code "45") (name "Net-(USB1-CC1)") (class "Default")
      (node (ref "R3") (pin "1") (pinfunction "1_1") (pintype "input"))
      (node (ref "USB1") (pin "4") (pinfunction "CC1_4") (pintype "unspecified"))
    )
    (net (code "46") (name "Net-(USB1-CC2)") (class "Default")
      (node (ref "R1") (pin "1") (pinfunction "1_1") (pintype "input"))
      (node (ref "USB1") (pin "10") (pinfunction "CC2_10") (pintype "unspecified"))
    )
    (net (code "47") (name "OSC32_IN") (class "Default")
      (node (ref "C10") (pin "1") (pinfunction "1_1") (pintype "input"))
      (node (ref "U3") (pin "3") (pinfunction "PC14-OSC32_IN_3") (pintype "unspecified"))
      (node (ref "X2") (pin "1") (pinfunction "OSC1_1") (pintype "unspecified"))
    )
    (net (code "48") (name "OSC32_OUT") (class "Default")
      (node (ref "C11") (pin "1") (pinfunction "1_1") (pintype "input"))
      (node (ref "U3") (pin "4") (pinfunction "PC15-OSC32_OUT_4") (pintype "unspecified"))
      (node (ref "X2") (pin "2") (pinfunction "OSC2_2") (pintype "unspecified"))
    )
    (net (code "49") (name "OSC_IN") (class "Default")
      (node (ref "C4") (pin "1") (pinfunction "1_1") (pintype "input"))
      (node (ref "U3") (pin "5") (pinfunction "PH0-OSC_IN_5") (pintype "unspecified"))
      (node (ref "X1") (pin "2") (pinfunction "OSC2_2") (pintype "input"))
    )
    (net (code "50") (name "OSC_OUT") (class "Default")
      (node (ref "C6") (pin "1") (pinfunction "1_1") (pintype "input"))
      (node (ref "U3") (pin "6") (pinfunction "PH1-OSC_OUT_6") (pintype "unspecified"))
      (node (ref "X1") (pin "1") (pinfunction "OSC1_1") (pintype "input"))
    )
    (net (code "51") (name "SWCLK") (class "Default")
      (node (ref "H1") (pin "3") (pinfunction "3_3") (pintype "unspecified"))
      (node (ref "U3") (pin "37") (pinfunction "PA14_37") (pintype "unspecified"))
    )
    (net (code "52") (name "SWDIO") (class "Default")
      (node (ref "H1") (pin "2") (pinfunction "2_2") (pintype "unspecified"))
      (node (ref "U3") (pin "34") (pinfunction "PA13_34") (pintype "unspecified"))
    )
    (net (code "53") (name "VBUS") (class "Default")
      (node (ref "F1") (pin "2") (pinfunction "2_2") (pintype "unspecified"))
      (node (ref "USB1") (pin "11") (pinfunction "VBUS_11") (pintype "unspecified"))
      (node (ref "USB1") (pin "2") (pinfunction "VBUS_2") (pintype "unspecified"))
    )
    (net (code "54") (name "unconnected-(H2-Pad4)") (class "Default")
      (node (ref "H2") (pin "4") (pinfunction "4_4") (pintype "input+no_connect"))
    )
    (net (code "55") (name "unconnected-(H2-Pad5)") (class "Default")
      (node (ref "H2") (pin "5") (pinfunction "5_5") (pintype "input+no_connect"))
    )
    (net (code "56") (name "unconnected-(P1-Pad1)") (class "Default")
      (node (ref "P1") (pin "1") (pinfunction "1_1") (pintype "input+no_connect"))
    )
    (net (code "57") (name "unconnected-(P1-Pad2)") (class "Default")
      (node (ref "P1") (pin "2") (pinfunction "2_2") (pintype "input+no_connect"))
    )
    (net (code "58") (name "unconnected-(P1-Pad3)") (class "Default")
      (node (ref "P1") (pin "3") (pinfunction "3_3") (pintype "input+no_connect"))
    )
    (net (code "59") (name "unconnected-(P1-Pad4)") (class "Default")
      (node (ref "P1") (pin "4") (pinfunction "4_4") (pintype "input+no_connect"))
    )
    (net (code "60") (name "unconnected-(P2-Pad1)") (class "Default")
      (node (ref "P2") (pin "1") (pinfunction "1_1") (pintype "input+no_connect"))
    )
    (net (code "61") (name "unconnected-(SCREW1-Pad1)") (class "Default")
      (node (ref "SCREW1") (pin "1") (pinfunction "1_1") (pintype "input+no_connect"))
    )
    (net (code "62") (name "unconnected-(SCREW2-Pad1)") (class "Default")
      (node (ref "SCREW2") (pin "1") (pinfunction "1_1") (pintype "input+no_connect"))
    )
    (net (code "63") (name "unconnected-(SCREW3-Pad1)") (class "Default")
      (node (ref "SCREW3") (pin "1") (pinfunction "1_1") (pintype "input+no_connect"))
    )
    (net (code "64") (name "unconnected-(SCREW4-Pad1)") (class "Default")
      (node (ref "SCREW4") (pin "1") (pinfunction "1_1") (pintype "input+no_connect"))
    )
    (net (code "65") (name "unconnected-(SW1-Pad3)") (class "Default")
      (node (ref "SW1") (pin "3") (pinfunction "3_3") (pintype "unspecified+no_connect"))
    )
    (net (code "66") (name "unconnected-(SW1-Pad4)") (class "Default")
      (node (ref "SW1") (pin "4") (pinfunction "4_4") (pintype "unspecified+no_connect"))
    )
    (net (code "67") (name "unconnected-(SW1-Pad5)") (class "Default")
      (node (ref "SW1") (pin "5") (pinfunction "5_5") (pintype "unspecified+no_connect"))
    )
    (net (code "68") (name "unconnected-(SW1-Pad6)") (class "Default")
      (node (ref "SW1") (pin "6") (pinfunction "6_6") (pintype "unspecified+no_connect"))
    )
    (net (code "69") (name "unconnected-(U2-CTS#-Pad9)") (class "Default")
      (node (ref "U2") (pin "9") (pinfunction "CTS#_9") (pintype "unspecified+no_connect"))
    )
    (net (code "70") (name "unconnected-(U2-DCD#-Pad12)") (class "Default")
      (node (ref "U2") (pin "12") (pinfunction "DCD#_12") (pintype "unspecified+no_connect"))
    )
    (net (code "71") (name "unconnected-(U2-DSR#-Pad10)") (class "Default")
      (node (ref "U2") (pin "10") (pinfunction "DSR#_10") (pintype "unspecified+no_connect"))
    )
    (net (code "72") (name "unconnected-(U2-DTR#-Pad13)") (class "Default")
      (node (ref "U2") (pin "13") (pinfunction "DTR#_13") (pintype "unspecified+no_connect"))
    )
    (net (code "73") (name "unconnected-(U2-NC.-Pad7)") (class "Default")
      (node (ref "U2") (pin "7") (pinfunction "NC._7") (pintype "unspecified+no_connect"))
    )
    (net (code "74") (name "unconnected-(U2-OUT#-Pad8)") (class "Default")
      (node (ref "U2") (pin "8") (pinfunction "OUT#_8") (pintype "unspecified+no_connect"))
    )
    (net (code "75") (name "unconnected-(U2-R232-Pad15)") (class "Default")
      (node (ref "U2") (pin "15") (pinfunction "R232_15") (pintype "unspecified+no_connect"))
    )
    (net (code "76") (name "unconnected-(U2-RI#-Pad11)") (class "Default")
      (node (ref "U2") (pin "11") (pinfunction "RI#_11") (pintype "unspecified+no_connect"))
    )
    (net (code "77") (name "unconnected-(U2-RTS#-Pad14)") (class "Default")
      (node (ref "U2") (pin "14") (pinfunction "RTS#_14") (pintype "unspecified+no_connect"))
    )
    (net (code "78") (name "unconnected-(U3-PA0-Pad10)") (class "Default")
      (node (ref "U3") (pin "10") (pinfunction "PA0_10") (pintype "unspecified+no_connect"))
    )
    (net (code "79") (name "unconnected-(U3-PA1-Pad11)") (class "Default")
      (node (ref "U3") (pin "11") (pinfunction "PA1_11") (pintype "unspecified+no_connect"))
    )
    (net (code "80") (name "unconnected-(U3-PA2-Pad12)") (class "Default")
      (node (ref "U3") (pin "12") (pinfunction "PA2_12") (pintype "unspecified+no_connect"))
    )
    (net (code "81") (name "unconnected-(U3-PB2-Pad20)") (class "Default")
      (node (ref "U3") (pin "20") (pinfunction "PB2_20") (pintype "unspecified+no_connect"))
    )
    (net (code "82") (name "unconnected-(U3-PB3-Pad39)") (class "Default")
      (node (ref "U3") (pin "39") (pinfunction "PB3_39") (pintype "unspecified+no_connect"))
    )
    (net (code "83") (name "unconnected-(U3-PB4-Pad40)") (class "Default")
      (node (ref "U3") (pin "40") (pinfunction "PB4_40") (pintype "unspecified+no_connect"))
    )
    (net (code "84") (name "unconnected-(U3-PB5-Pad41)") (class "Default")
      (node (ref "U3") (pin "41") (pinfunction "PB5_41") (pintype "unspecified+no_connect"))
    )
    (net (code "85") (name "unconnected-(U3-PB6-Pad42)") (class "Default")
      (node (ref "U3") (pin "42") (pinfunction "PB6_42") (pintype "unspecified+no_connect"))
    )
    (net (code "86") (name "unconnected-(U3-PB7-Pad43)") (class "Default")
      (node (ref "U3") (pin "43") (pinfunction "PB7_43") (pintype "unspecified+no_connect"))
    )
    (net (code "87") (name "unconnected-(U3-PB8-Pad45)") (class "Default")
      (node (ref "U3") (pin "45") (pinfunction "PB8_45") (pintype "unspecified+no_connect"))
    )
    (net (code "88") (name "unconnected-(U3-PB9-Pad46)") (class "Default")
      (node (ref "U3") (pin "46") (pinfunction "PB9_46") (pintype "unspecified+no_connect"))
    )
    (net (code "89") (name "unconnected-(U3-PC13-Pad2)") (class "Default")
      (node (ref "U3") (pin "2") (pinfunction "PC13_2") (pintype "unspecified+no_connect"))
    )
    (net (code "90") (name "unconnected-(USB1-SBU1-Pad9)") (class "Default")
      (node (ref "USB1") (pin "9") (pinfunction "SBU1_9") (pintype "unspecified+no_connect"))
    )
    (net (code "91") (name "unconnected-(USB1-SBU2-Pad3)") (class "Default")
      (node (ref "USB1") (pin "3") (pinfunction "SBU2_3") (pintype "unspecified+no_connect"))
    )
  )
)
